# ECE411.net
KiCad netlist of a schematic drawn in EAGLE
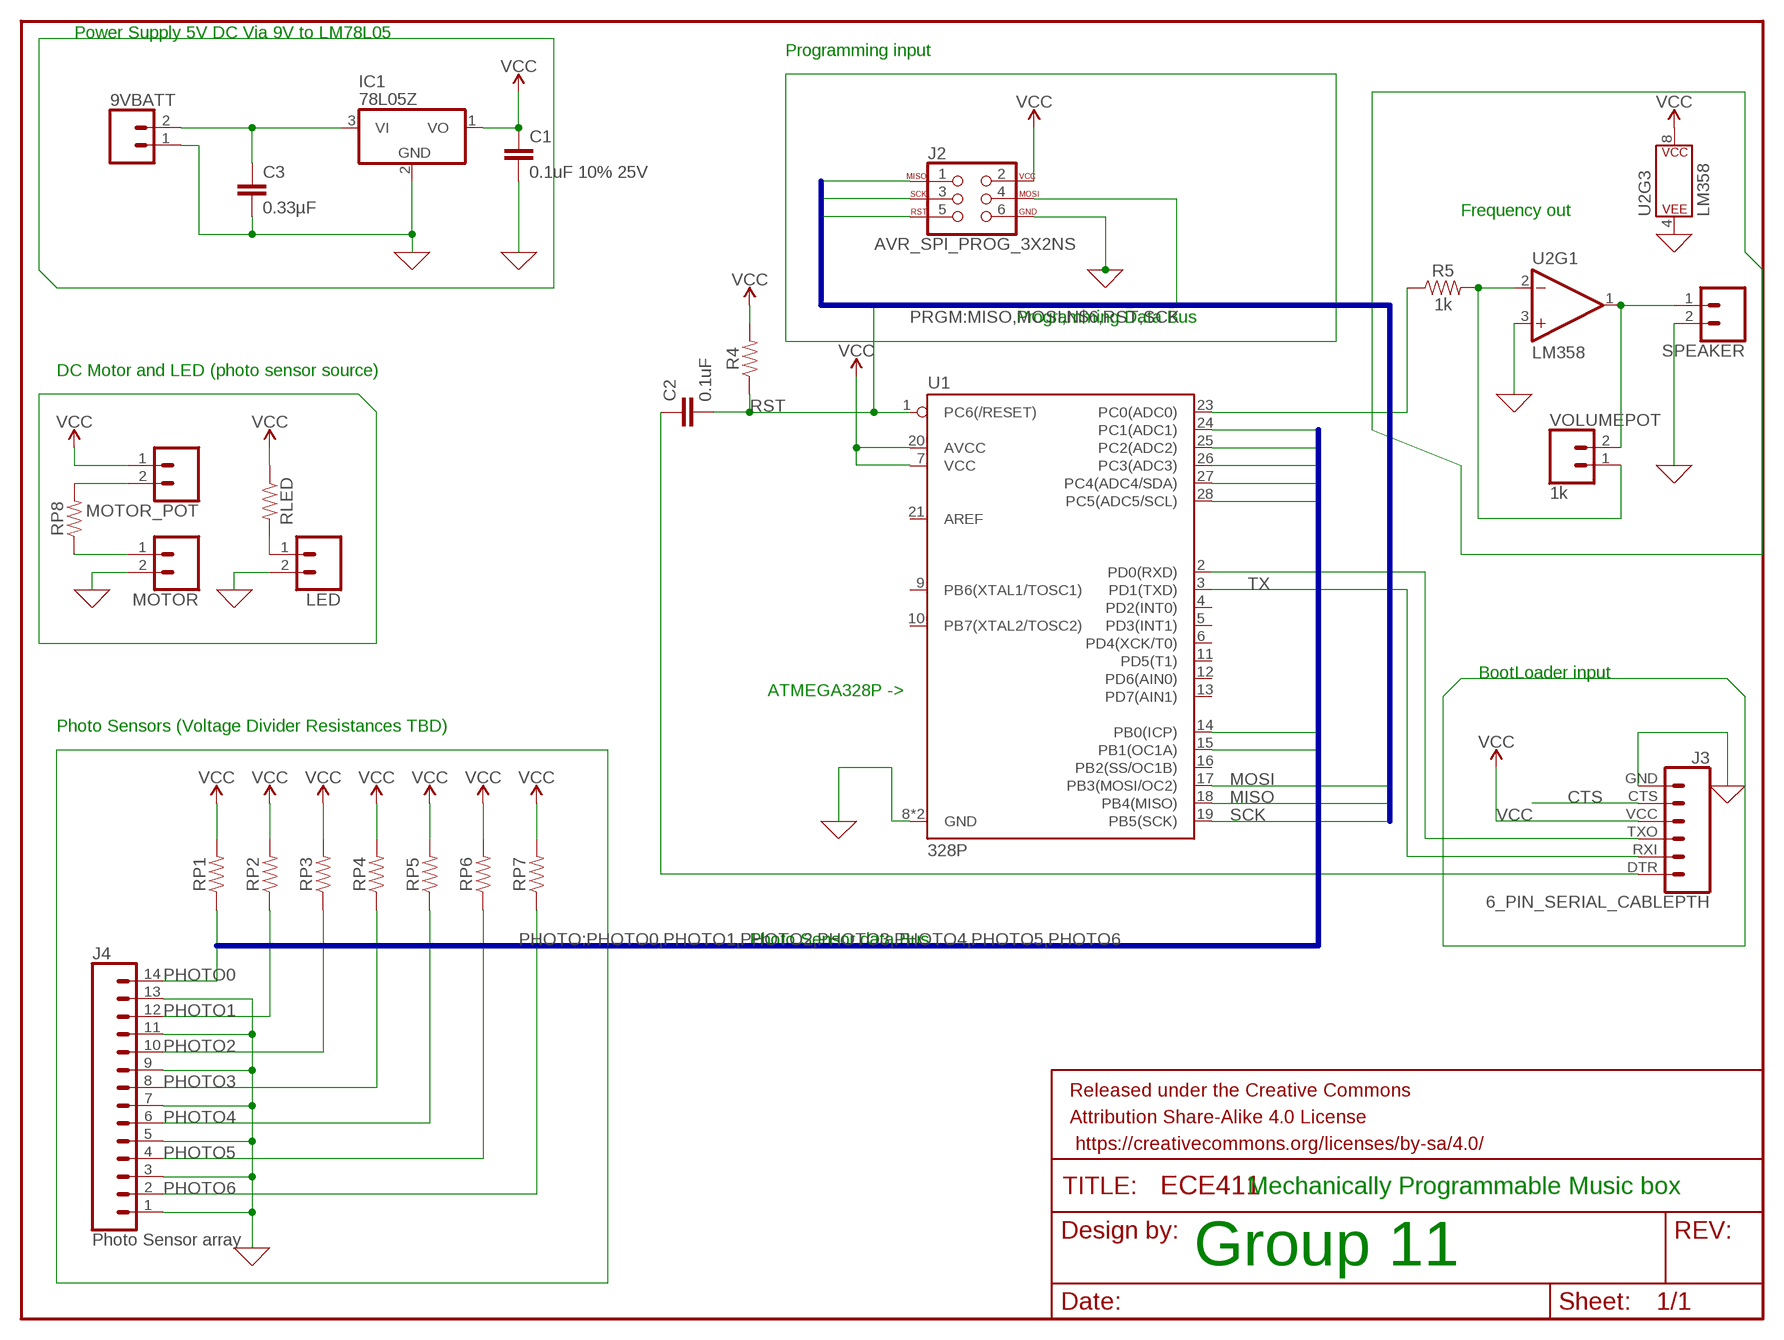
[diagram p0: schematic, sheet 1]

(export (version "E")
  (design (tool "Eeschema 10.0.6"))
  (components
    (comp (ref "9VBATT")
      (value "CONN_02")
      (footprint "eagle-import:1X02")
      (libsource (lib "eagle-import") (part "CONN_02"))
    )
    (comp (ref "C1")
      (value "0.1uF 10% 25V")
      (footprint "eagle-import:0603")
      (libsource (lib "eagle-import") (part "0.1UF-0603-25V-(+80/-20%)"))
    )
    (comp (ref "C2")
      (value "0.1uF")
      (footprint "eagle-import:0603")
      (libsource (lib "eagle-import") (part "0.1UF-0603-25V-(+80/-20%)"))
    )
    (comp (ref "C3")
      (value "0.33µF")
      (footprint "eagle-import:0805")
      (libsource (lib "eagle-import") (part "0.33UF/330NF-0805-50V-10%"))
    )
    (comp (ref "FRAME1")
      (value "FRAME-LETTER")
      (footprint "eagle-import:CREATIVE_COMMONS")
      (libsource (lib "eagle-import") (part "FRAME-LETTER"))
    )
    (comp (ref "IC1")
      (value "78L05Z")
      (footprint "eagle-import:TO92")
      (libsource (lib "eagle-import") (part "78ZL05"))
    )
    (comp (ref "J2")
      (value "AVR_SPI_PROG_3X2NS")
      (footprint "eagle-import:2X3-NS")
      (libsource (lib "eagle-import") (part "AVR_SPI_PROG_3X2NS"))
    )
    (comp (ref "J3")
      (value "6_PIN_SERIAL_CABLEPTH")
      (footprint "eagle-import:FTDI_BASIC")
      (libsource (lib "eagle-import") (part "6_PIN_SERIAL_CABLEPTH"))
    )
    (comp (ref "J4")
      (value "Photo Sensor array")
      (footprint "eagle-import:1X14")
      (libsource (lib "eagle-import") (part "CONN_14"))
    )
    (comp (ref "LED")
      (value "CONN_02")
      (footprint "eagle-import:1X02")
      (libsource (lib "eagle-import") (part "CONN_02"))
    )
    (comp (ref "MOTOR")
      (value "CONN_02")
      (footprint "eagle-import:1X02")
      (libsource (lib "eagle-import") (part "CONN_02"))
    )
    (comp (ref "MOTOR_POT")
      (value "CONN_02")
      (footprint "eagle-import:1X02")
      (libsource (lib "eagle-import") (part "CONN_02"))
    )
    (comp (ref "R4")
      (value "RESISTOR0805")
      (footprint "eagle-import:0805")
      (libsource (lib "eagle-import") (part "RESISTOR0805"))
    )
    (comp (ref "R5")
      (value "1k")
      (footprint "eagle-import:0603")
      (libsource (lib "eagle-import") (part "1KOHM-0603-1/10W-1%"))
    )
    (comp (ref "RLED")
      (value "RESISTOR0603")
      (footprint "eagle-import:0603")
      (libsource (lib "eagle-import") (part "RESISTOR0603"))
    )
    (comp (ref "RP1")
      (value "RESISTOR0603")
      (footprint "eagle-import:0603")
      (libsource (lib "eagle-import") (part "RESISTOR0603"))
    )
    (comp (ref "RP2")
      (value "RESISTOR0603")
      (footprint "eagle-import:0603")
      (libsource (lib "eagle-import") (part "RESISTOR0603"))
    )
    (comp (ref "RP3")
      (value "RESISTOR0603")
      (footprint "eagle-import:0603")
      (libsource (lib "eagle-import") (part "RESISTOR0603"))
    )
    (comp (ref "RP4")
      (value "RESISTOR0603")
      (footprint "eagle-import:0603")
      (libsource (lib "eagle-import") (part "RESISTOR0603"))
    )
    (comp (ref "RP5")
      (value "RESISTOR0603")
      (footprint "eagle-import:0603")
      (libsource (lib "eagle-import") (part "RESISTOR0603"))
    )
    (comp (ref "RP6")
      (value "RESISTOR0603")
      (footprint "eagle-import:0603")
      (libsource (lib "eagle-import") (part "RESISTOR0603"))
    )
    (comp (ref "RP7")
      (value "RESISTOR0603")
      (footprint "eagle-import:0603")
      (libsource (lib "eagle-import") (part "RESISTOR0603"))
    )
    (comp (ref "RP8")
      (value "RESISTOR0603")
      (footprint "eagle-import:0603")
      (libsource (lib "eagle-import") (part "RESISTOR0603"))
    )
    (comp (ref "SPEAKER")
      (value "CONN_02")
      (footprint "eagle-import:1X02")
      (libsource (lib "eagle-import") (part "CONN_02"))
    )
    (comp (ref "U1")
      (value "328P")
      (footprint "eagle-import:DIP28")
      (libsource (lib "eagle-import") (part "ATMEGA328P_PDIP"))
    )
    (comp (ref "U2")
      (value "LM358")
      (footprint "eagle-import:DIP08")
      (libsource (lib "eagle-import") (part "LM358"))
    )
    (comp (ref "VOLUMEPOT")
      (value "1k")
      (footprint "eagle-import:1X02")
      (libsource (lib "eagle-import") (part "CONN_02"))
    )
  )
  (nets
    (net (code "4") (name "/CTS") (class "Default")
      (node (ref "J3") (pin "CTS") (pinfunction "5_CTS") (pintype "passive"))
    )
    (net (code "5") (name "/MISO") (class "Default")
      (node (ref "J2") (pin "1") (pinfunction "1_1") (pintype "passive"))
      (node (ref "U1") (pin "18") (pinfunction "PB4(MISO)_18") (pintype "bidirectional"))
    )
    (net (code "6") (name "/MOSI") (class "Default")
      (node (ref "J2") (pin "4") (pinfunction "4_4") (pintype "passive"))
      (node (ref "U1") (pin "17") (pinfunction "PB3(MOSI/OC2)_17") (pintype "bidirectional"))
    )
    (net (code "7") (name "/PHOTO0") (class "Default")
      (node (ref "J4") (pin "14") (pinfunction "14_14") (pintype "passive"))
      (node (ref "RP1") (pin "1") (pinfunction "1_1") (pintype "passive"))
      (node (ref "U1") (pin "24") (pinfunction "PC1(ADC1)_24") (pintype "bidirectional"))
    )
    (net (code "8") (name "/PHOTO1") (class "Default")
      (node (ref "J4") (pin "12") (pinfunction "12_12") (pintype "passive"))
      (node (ref "RP2") (pin "1") (pinfunction "1_1") (pintype "passive"))
      (node (ref "U1") (pin "25") (pinfunction "PC2(ADC2)_25") (pintype "bidirectional"))
    )
    (net (code "9") (name "/PHOTO2") (class "Default")
      (node (ref "J4") (pin "10") (pinfunction "10_10") (pintype "passive"))
      (node (ref "RP3") (pin "1") (pinfunction "1_1") (pintype "passive"))
      (node (ref "U1") (pin "26") (pinfunction "PC3(ADC3)_26") (pintype "bidirectional"))
    )
    (net (code "10") (name "/PHOTO3") (class "Default")
      (node (ref "J4") (pin "8") (pinfunction "8_8") (pintype "passive"))
      (node (ref "RP4") (pin "1") (pinfunction "1_1") (pintype "passive"))
      (node (ref "U1") (pin "27") (pinfunction "PC4(ADC4/SDA)_27") (pintype "bidirectional"))
    )
    (net (code "11") (name "/PHOTO4") (class "Default")
      (node (ref "J4") (pin "6") (pinfunction "6_6") (pintype "passive"))
      (node (ref "RP5") (pin "1") (pinfunction "1_1") (pintype "passive"))
      (node (ref "U1") (pin "28") (pinfunction "PC5(ADC5/SCL)_28") (pintype "bidirectional"))
    )
    (net (code "12") (name "/PHOTO5") (class "Default")
      (node (ref "J4") (pin "4") (pinfunction "4_4") (pintype "passive"))
      (node (ref "RP6") (pin "1") (pinfunction "1_1") (pintype "passive"))
      (node (ref "U1") (pin "14") (pinfunction "PB0(ICP)_14") (pintype "bidirectional"))
    )
    (net (code "13") (name "/PHOTO6") (class "Default")
      (node (ref "J4") (pin "2") (pinfunction "2_2") (pintype "passive"))
      (node (ref "RP7") (pin "1") (pinfunction "1_1") (pintype "passive"))
      (node (ref "U1") (pin "15") (pinfunction "PB1(OC1A)_15") (pintype "bidirectional"))
    )
    (net (code "14") (name "/RST") (class "Default")
      (node (ref "C2") (pin "2") (pinfunction "2_2") (pintype "passive"))
      (node (ref "J2") (pin "5") (pinfunction "5_5") (pintype "passive"))
      (node (ref "R4") (pin "1") (pinfunction "1_1") (pintype "passive"))
      (node (ref "U1") (pin "1") (pinfunction "PC6(/RESET)_1") (pintype "bidirectional"))
    )
    (net (code "15") (name "/SCK") (class "Default")
      (node (ref "J2") (pin "3") (pinfunction "3_3") (pintype "passive"))
      (node (ref "U1") (pin "19") (pinfunction "PB5(SCK)_19") (pintype "bidirectional"))
    )
    (net (code "16") (name "/TX") (class "Default")
      (node (ref "J3") (pin "RXI") (pinfunction "2_RXI") (pintype "passive"))
      (node (ref "U1") (pin "3") (pinfunction "PD1(TXD)_3") (pintype "bidirectional"))
    )
    (net (code "19") (name "GND") (class "Default")
      (node (ref "9VBATT") (pin "1") (pinfunction "1_1") (pintype "passive"))
      (node (ref "C1") (pin "2") (pinfunction "2_2") (pintype "passive"))
      (node (ref "C3") (pin "2") (pinfunction "2_2") (pintype "passive"))
      (node (ref "IC1") (pin "2") (pinfunction "GND_2") (pintype "passive"))
      (node (ref "J2") (pin "6") (pinfunction "6_6") (pintype "passive"))
      (node (ref "J3") (pin "GND") (pinfunction "6_GND") (pintype "passive"))
      (node (ref "J4") (pin "1") (pinfunction "1_1") (pintype "passive"))
      (node (ref "J4") (pin "11") (pinfunction "11_11") (pintype "passive"))
      (node (ref "J4") (pin "13") (pinfunction "13_13") (pintype "passive"))
      (node (ref "J4") (pin "3") (pinfunction "3_3") (pintype "passive"))
      (node (ref "J4") (pin "5") (pinfunction "5_5") (pintype "passive"))
      (node (ref "J4") (pin "7") (pinfunction "7_7") (pintype "passive"))
      (node (ref "J4") (pin "9") (pinfunction "9_9") (pintype "passive"))
      (node (ref "LED") (pin "2") (pinfunction "2_2") (pintype "passive"))
      (node (ref "MOTOR") (pin "2") (pinfunction "2_2") (pintype "passive"))
      (node (ref "SPEAKER") (pin "2") (pinfunction "2_2") (pintype "passive"))
      (node (ref "U1") (pin "22") (pinfunction "GND_22") (pintype "bidirectional"))
      (node (ref "U1") (pin "8") (pinfunction "GND_8") (pintype "bidirectional"))
      (node (ref "U2") (pin "3") (pinfunction "+IN_3") (pintype "input"))
      (node (ref "U2") (pin "4") (pinfunction "P$V-_4") (pintype "bidirectional"))
    )
    (net (code "20") (name "Net-(IC1-VI)") (class "Default")
      (node (ref "9VBATT") (pin "2") (pinfunction "2_2") (pintype "passive"))
      (node (ref "C3") (pin "1") (pinfunction "1_1") (pintype "passive"))
      (node (ref "IC1") (pin "3") (pinfunction "VI_3") (pintype "input"))
    )
    (net (code "21") (name "Net-(J3-1)") (class "Default")
      (node (ref "C2") (pin "1") (pinfunction "1_1") (pintype "passive"))
      (node (ref "J3") (pin "DTR") (pinfunction "1_DTR") (pintype "passive"))
    )
    (net (code "22") (name "Net-(J3-3)") (class "Default")
      (node (ref "J3") (pin "TXO") (pinfunction "3_TXO") (pintype "passive"))
      (node (ref "U1") (pin "2") (pinfunction "PD0(RXD)_2") (pintype "bidirectional"))
    )
    (net (code "23") (name "Net-(LED-Pad1)") (class "Default")
      (node (ref "LED") (pin "1") (pinfunction "1_1") (pintype "passive"))
      (node (ref "RLED") (pin "2") (pinfunction "2_2") (pintype "passive"))
    )
    (net (code "24") (name "Net-(MOTOR-Pad1)") (class "Default")
      (node (ref "MOTOR") (pin "1") (pinfunction "1_1") (pintype "passive"))
      (node (ref "RP8") (pin "1") (pinfunction "1_1") (pintype "passive"))
    )
    (net (code "25") (name "Net-(MOTOR_POT-Pad2)") (class "Default")
      (node (ref "MOTOR_POT") (pin "2") (pinfunction "2_2") (pintype "passive"))
      (node (ref "RP8") (pin "2") (pinfunction "2_2") (pintype "passive"))
    )
    (net (code "26") (name "Net-(U1-PC0(ADC0))") (class "Default")
      (node (ref "R5") (pin "1") (pinfunction "1_1") (pintype "passive"))
      (node (ref "U1") (pin "23") (pinfunction "PC0(ADC0)_23") (pintype "bidirectional"))
    )
    (net (code "27") (name "Net-(U2A--IN)") (class "Default")
      (node (ref "R5") (pin "2") (pinfunction "2_2") (pintype "passive"))
      (node (ref "U2") (pin "2") (pinfunction "-IN_2") (pintype "input"))
      (node (ref "VOLUMEPOT") (pin "1") (pinfunction "1_1") (pintype "passive"))
    )
    (net (code "28") (name "Net-(U2A-OUT)") (class "Default")
      (node (ref "SPEAKER") (pin "1") (pinfunction "1_1") (pintype "passive"))
      (node (ref "U2") (pin "1") (pinfunction "OUT_1") (pintype "output"))
      (node (ref "VOLUMEPOT") (pin "2") (pinfunction "2_2") (pintype "passive"))
    )
    (net (code "29") (name "VCC") (class "Default")
      (node (ref "C1") (pin "1") (pinfunction "1_1") (pintype "passive"))
      (node (ref "IC1") (pin "1") (pinfunction "VO_1") (pintype "passive"))
      (node (ref "J2") (pin "2") (pinfunction "2_2") (pintype "passive"))
      (node (ref "J3") (pin "VCC") (pinfunction "4_VCC") (pintype "passive"))
      (node (ref "MOTOR_POT") (pin "1") (pinfunction "1_1") (pintype "passive"))
      (node (ref "R4") (pin "2") (pinfunction "2_2") (pintype "passive"))
      (node (ref "RLED") (pin "1") (pinfunction "1_1") (pintype "passive"))
      (node (ref "RP1") (pin "2") (pinfunction "2_2") (pintype "passive"))
      (node (ref "RP2") (pin "2") (pinfunction "2_2") (pintype "passive"))
      (node (ref "RP3") (pin "2") (pinfunction "2_2") (pintype "passive"))
      (node (ref "RP4") (pin "2") (pinfunction "2_2") (pintype "passive"))
      (node (ref "RP5") (pin "2") (pinfunction "2_2") (pintype "passive"))
      (node (ref "RP6") (pin "2") (pinfunction "2_2") (pintype "passive"))
      (node (ref "RP7") (pin "2") (pinfunction "2_2") (pintype "passive"))
      (node (ref "U1") (pin "20") (pinfunction "AVCC_20") (pintype "bidirectional"))
      (node (ref "U1") (pin "7") (pinfunction "VCC_7") (pintype "bidirectional"))
      (node (ref "U2") (pin "8") (pinfunction "P$V+_8") (pintype "bidirectional"))
    )
    (net (code "30") (name "unconnected-(U1-AREF-Pad21)") (class "Default")
      (node (ref "U1") (pin "21") (pinfunction "AREF_21") (pintype "bidirectional"))
    )
    (net (code "31") (name "unconnected-(U1-PB2(SS{slash}OC1B)-Pad16)") (class "Default")
      (node (ref "U1") (pin "16") (pinfunction "PB2(SS/OC1B)_16") (pintype "bidirectional"))
    )
    (net (code "32") (name "unconnected-(U1-PB6(XTAL1{slash}TOSC1)-Pad9)") (class "Default")
      (node (ref "U1") (pin "9") (pinfunction "PB6(XTAL1/TOSC1)_9") (pintype "bidirectional"))
    )
    (net (code "33") (name "unconnected-(U1-PB7(XTAL2{slash}TOSC2)-Pad10)") (class "Default")
      (node (ref "U1") (pin "10") (pinfunction "PB7(XTAL2/TOSC2)_10") (pintype "bidirectional"))
    )
    (net (code "34") (name "unconnected-(U1-PD2(INT0)-Pad4)") (class "Default")
      (node (ref "U1") (pin "4") (pinfunction "PD2(INT0)_4") (pintype "bidirectional"))
    )
    (net (code "35") (name "unconnected-(U1-PD3(INT1)-Pad5)") (class "Default")
      (node (ref "U1") (pin "5") (pinfunction "PD3(INT1)_5") (pintype "bidirectional"))
    )
    (net (code "36") (name "unconnected-(U1-PD4(XCK{slash}T0)-Pad6)") (class "Default")
      (node (ref "U1") (pin "6") (pinfunction "PD4(XCK/T0)_6") (pintype "bidirectional"))
    )
    (net (code "37") (name "unconnected-(U1-PD5(T1)-Pad11)") (class "Default")
      (node (ref "U1") (pin "11") (pinfunction "PD5(T1)_11") (pintype "bidirectional"))
    )
    (net (code "38") (name "unconnected-(U1-PD6(AIN0)-Pad12)") (class "Default")
      (node (ref "U1") (pin "12") (pinfunction "PD6(AIN0)_12") (pintype "bidirectional"))
    )
    (net (code "39") (name "unconnected-(U1-PD7(AIN1)-Pad13)") (class "Default")
      (node (ref "U1") (pin "13") (pinfunction "PD7(AIN1)_13") (pintype "bidirectional"))
    )
  )
)
